# VGAX_board_rev_12_PAPER_VERSION_option_2.net
KiCad netlist of a schematic drawn in EAGLE
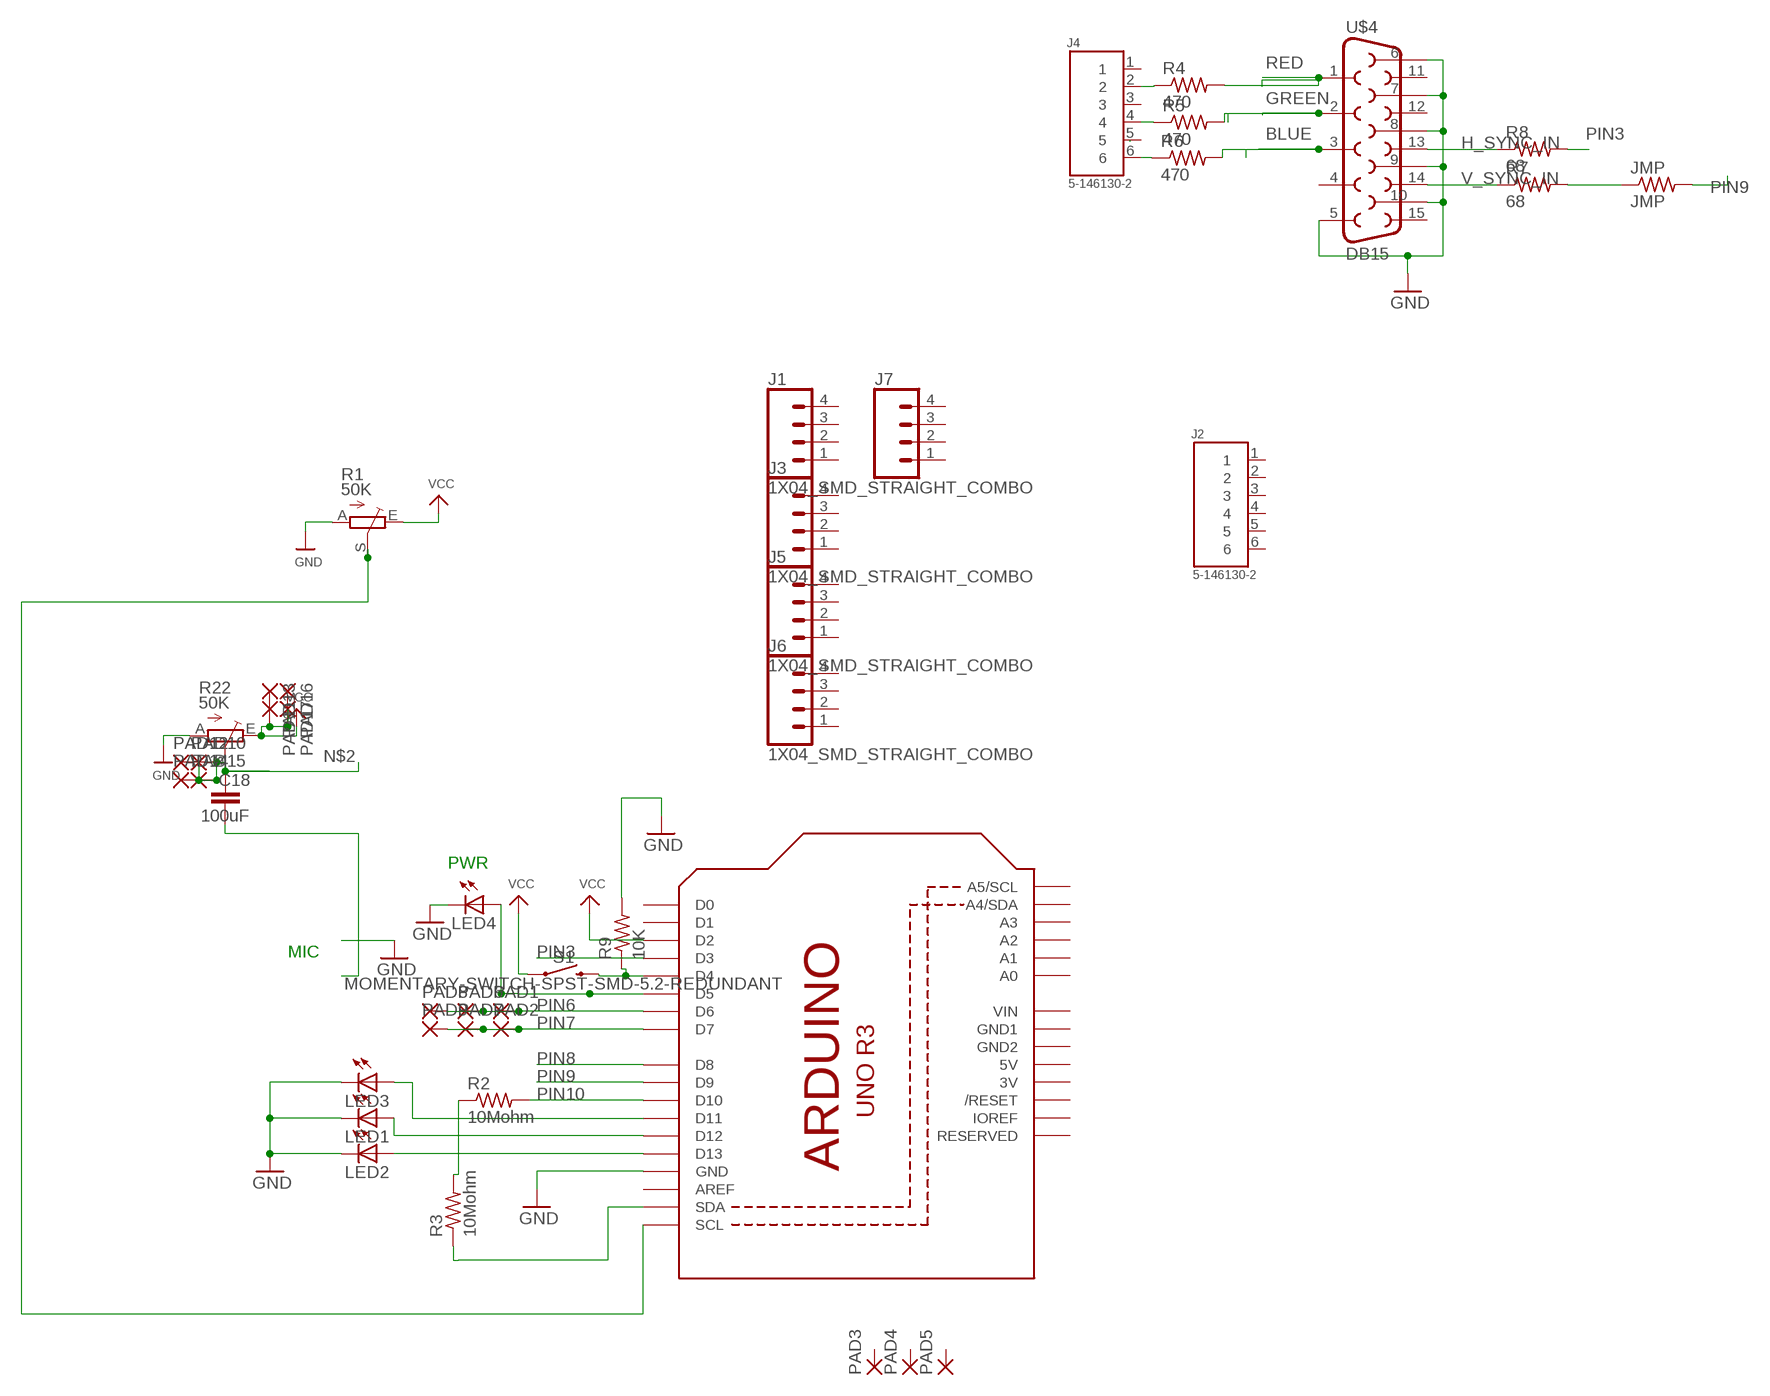
[diagram p0: schematic, sheet 1]

(export (version "E")
  (design (tool "Eeschema 10.0.6"))
  (components
    (comp (ref "C18")
      (value "100uF")
      (footprint "eagle-import:1206")
      (libsource (lib "eagle-import") (part "1.0UF-1206-50V-10%"))
    )
    (comp (ref "J1")
      (value "1X04_SMD_STRAIGHT_COMBO")
      (footprint "eagle-import:1X04_SMD_VERTICAL_COMBO")
      (libsource (lib "eagle-import") (part "CONN_04SMD_STRAIGHT_COMBO"))
    )
    (comp (ref "J2")
      (value "5-146130-2")
      (footprint "eagle-import:5-146130-2")
      (fields
        (field (name "DIGIKEY_PART_NUMBER") "5-146130-2-ND")
        (field (name "MANUFACTURER") "TE Connectivity AMP Connectors")
        (field (name "CREATED_BY") "PCBLayout.com")
      )
      (libsource (lib "eagle-import") (part "5-146130-2"))
    )
    (comp (ref "J3")
      (value "1X04_SMD_STRAIGHT_COMBO")
      (footprint "eagle-import:1X04_SMD_VERTICAL_COMBO")
      (libsource (lib "eagle-import") (part "CONN_04SMD_STRAIGHT_COMBO"))
    )
    (comp (ref "J4")
      (value "5-146130-2")
      (footprint "eagle-import:5-146130-2")
      (fields
        (field (name "DIGIKEY_PART_NUMBER") "5-146130-2-ND")
        (field (name "MANUFACTURER") "TE Connectivity AMP Connectors")
        (field (name "CREATED_BY") "PCBLayout.com")
      )
      (libsource (lib "eagle-import") (part "5-146130-2"))
    )
    (comp (ref "J5")
      (value "1X04_SMD_STRAIGHT_COMBO")
      (footprint "eagle-import:1X04_SMD_VERTICAL_COMBO")
      (libsource (lib "eagle-import") (part "CONN_04SMD_STRAIGHT_COMBO"))
    )
    (comp (ref "J6")
      (value "1X04_SMD_STRAIGHT_COMBO")
      (footprint "eagle-import:1X04_SMD_VERTICAL_COMBO")
      (libsource (lib "eagle-import") (part "CONN_04SMD_STRAIGHT_COMBO"))
    )
    (comp (ref "J7")
      (value "1X04_SMD_STRAIGHT_COMBO")
      (footprint "eagle-import:1X04_SMD_VERTICAL_COMBO")
      (libsource (lib "eagle-import") (part "CONN_04SMD_STRAIGHT_COMBO"))
    )
    (comp (ref "JMP")
      (value "JMP")
      (footprint "eagle-import:M1206")
      (libsource (lib "eagle-import") (part "R-US_M1206"))
    )
    (comp (ref "LED1")
      (value "LEDCHIPLED_1206")
      (footprint "eagle-import:CHIPLED_1206")
      (libsource (lib "eagle-import") (part "LEDCHIPLED_1206"))
    )
    (comp (ref "LED2")
      (value "LEDCHIPLED_1206")
      (footprint "eagle-import:CHIPLED_1206")
      (libsource (lib "eagle-import") (part "LEDCHIPLED_1206"))
    )
    (comp (ref "LED3")
      (value "LEDCHIPLED_1206")
      (footprint "eagle-import:CHIPLED_1206")
      (libsource (lib "eagle-import") (part "LEDCHIPLED_1206"))
    )
    (comp (ref "LED4")
      (value "LEDCHIPLED_1206")
      (footprint "eagle-import:CHIPLED_1206")
      (libsource (lib "eagle-import") (part "LEDCHIPLED_1206"))
    )
    (comp (ref "PAD1")
      (value "SMD2")
      (footprint "eagle-import:SMD1,27-2,54")
      (libsource (lib "eagle-import") (part "SMD2"))
    )
    (comp (ref "PAD2")
      (value "SMD2")
      (footprint "eagle-import:SMD1,27-2,54")
      (libsource (lib "eagle-import") (part "SMD2"))
    )
    (comp (ref "PAD3")
      (value "SMD2")
      (footprint "eagle-import:SMD1,27-2,54")
      (libsource (lib "eagle-import") (part "SMD2"))
    )
    (comp (ref "PAD4")
      (value "SMD2")
      (footprint "eagle-import:SMD1,27-2,54")
      (libsource (lib "eagle-import") (part "SMD2"))
    )
    (comp (ref "PAD5")
      (value "SMD2")
      (footprint "eagle-import:SMD1,27-2,54")
      (libsource (lib "eagle-import") (part "SMD2"))
    )
    (comp (ref "PAD6")
      (value "SMD2")
      (footprint "eagle-import:SMD1,27-2,54")
      (libsource (lib "eagle-import") (part "SMD2"))
    )
    (comp (ref "PAD7")
      (value "SMD2")
      (footprint "eagle-import:SMD1,27-2,54")
      (libsource (lib "eagle-import") (part "SMD2"))
    )
    (comp (ref "PAD8")
      (value "SMD2")
      (footprint "eagle-import:SMD1,27-2,54")
      (libsource (lib "eagle-import") (part "SMD2"))
    )
    (comp (ref "PAD9")
      (value "SMD2")
      (footprint "eagle-import:SMD1,27-2,54")
      (libsource (lib "eagle-import") (part "SMD2"))
    )
    (comp (ref "PAD10")
      (value "SMD2")
      (footprint "eagle-import:SMD1,27-2,54")
      (libsource (lib "eagle-import") (part "SMD2"))
    )
    (comp (ref "PAD11")
      (value "SMD2")
      (footprint "eagle-import:SMD1,27-2,54")
      (libsource (lib "eagle-import") (part "SMD2"))
    )
    (comp (ref "PAD12")
      (value "SMD2")
      (footprint "eagle-import:SMD1,27-2,54")
      (libsource (lib "eagle-import") (part "SMD2"))
    )
    (comp (ref "PAD13")
      (value "SMD2")
      (footprint "eagle-import:SMD1,27-2,54")
      (libsource (lib "eagle-import") (part "SMD2"))
    )
    (comp (ref "PAD14")
      (value "SMD2")
      (footprint "eagle-import:SMD1,27-2,54")
      (libsource (lib "eagle-import") (part "SMD2"))
    )
    (comp (ref "PAD15")
      (value "SMD2")
      (footprint "eagle-import:SMD1,27-2,54")
      (libsource (lib "eagle-import") (part "SMD2"))
    )
    (comp (ref "PAD16")
      (value "SMD2")
      (footprint "eagle-import:SMD1,27-2,54")
      (libsource (lib "eagle-import") (part "SMD2"))
    )
    (comp (ref "PAD17")
      (value "SMD2")
      (footprint "eagle-import:SMD1,27-2,54")
      (libsource (lib "eagle-import") (part "SMD2"))
    )
    (comp (ref "R1")
      (value "50K")
      (footprint "eagle-import:CA9V")
      (libsource (lib "eagle-import") (part "TRIM_EU-CA9V"))
    )
    (comp (ref "R2")
      (value "10Mohm")
      (footprint "eagle-import:M1206")
      (libsource (lib "eagle-import") (part "R-US_M1206"))
    )
    (comp (ref "R3")
      (value "10Mohm")
      (footprint "eagle-import:M1206")
      (libsource (lib "eagle-import") (part "R-US_M1206"))
    )
    (comp (ref "R4")
      (value "470")
      (footprint "eagle-import:M1206")
      (libsource (lib "eagle-import") (part "R-US_M1206"))
    )
    (comp (ref "R5")
      (value "470")
      (footprint "eagle-import:M1206")
      (libsource (lib "eagle-import") (part "R-US_M1206"))
    )
    (comp (ref "R6")
      (value "470")
      (footprint "eagle-import:M1206")
      (libsource (lib "eagle-import") (part "R-US_M1206"))
    )
    (comp (ref "R7")
      (value "68")
      (footprint "eagle-import:M1206")
      (libsource (lib "eagle-import") (part "R-US_M1206"))
    )
    (comp (ref "R8")
      (value "68")
      (footprint "eagle-import:M1206")
      (libsource (lib "eagle-import") (part "R-US_M1206"))
    )
    (comp (ref "R9")
      (value "10K")
      (footprint "eagle-import:M1206")
      (libsource (lib "eagle-import") (part "R-US_M1206"))
    )
    (comp (ref "R22")
      (value "50K")
      (footprint "eagle-import:CA9V")
      (libsource (lib "eagle-import") (part "TRIM_EU-CA9V"))
    )
    (comp (ref "S1")
      (value "MOMENTARY-SWITCH-SPST-SMD-5.2-REDUNDANT")
      (footprint "eagle-import:TACTILE_SWITCH_SMD_5.2MM")
      (libsource (lib "eagle-import") (part "MOMENTARY-SWITCH-SPST-SMD-5.2-REDUNDANT"))
    )
    (comp (ref "U$4")
      (value "DB15")
      (footprint "eagle-import:DB15")
      (libsource (lib "eagle-import") (part "DB15"))
    )
    (comp (ref "U1")
      (value "ARDUINOR3-BPLACE")
      (footprint "eagle-import:ARDUINOR3-BPLACE")
      (libsource (lib "eagle-import") (part "ARDUINOR3-BPLACE"))
    )
  )
  (nets
    (net (code "1") (name "/3V") (class "Default")
      (node (ref "U1") (pin "3V") (pinfunction "3V_3V") (pintype "power_in"))
    )
    (net (code "2") (name "/5V") (class "Default")
      (node (ref "U1") (pin "5V") (pinfunction "5V_5V") (pintype "power_in"))
    )
    (net (code "3") (name "/BLUE") (class "Default")
      (node (ref "R6") (pin "2") (pinfunction "2_2") (pintype "passive"))
      (node (ref "U$4") (pin "3") (pinfunction "3_3") (pintype "passive"))
    )
    (net (code "4") (name "/GND1") (class "Default")
      (node (ref "U1") (pin "GND1") (pinfunction "GND1_GND1") (pintype "power_in"))
    )
    (net (code "5") (name "/GND2") (class "Default")
      (node (ref "U1") (pin "GND2") (pinfunction "GND2_GND2") (pintype "power_in"))
    )
    (net (code "6") (name "/GREEN") (class "Default")
      (node (ref "R5") (pin "2") (pinfunction "2_2") (pintype "passive"))
      (node (ref "U$4") (pin "2") (pinfunction "2_2") (pintype "passive"))
    )
    (net (code "7") (name "/H_SYNC_IN") (class "Default")
      (node (ref "R8") (pin "1") (pinfunction "1_1") (pintype "passive"))
      (node (ref "U$4") (pin "13") (pinfunction "13_13") (pintype "passive"))
    )
    (net (code "8") (name "/N$2") (class "Default")
      (node (ref "C18") (pin "1") (pinfunction "1_1") (pintype "passive"))
      (node (ref "PAD10") (pin "1") (pinfunction "P_1") (pintype "passive"))
      (node (ref "PAD12") (pin "1") (pinfunction "P_1") (pintype "passive"))
      (node (ref "PAD14") (pin "1") (pinfunction "P_1") (pintype "passive"))
      (node (ref "PAD15") (pin "1") (pinfunction "P_1") (pintype "passive"))
      (node (ref "R22") (pin "S") (pinfunction "S_S") (pintype "passive"))
    )
    (net (code "9") (name "/PIN3") (class "Default")
      (node (ref "R8") (pin "2") (pinfunction "2_2") (pintype "passive"))
      (node (ref "U1") (pin "D3") (pinfunction "D3_D3") (pintype "bidirectional"))
    )
    (net (code "10") (name "/PIN6") (class "Default")
      (node (ref "PAD1") (pin "1") (pinfunction "P_1") (pintype "passive"))
      (node (ref "PAD6") (pin "1") (pinfunction "P_1") (pintype "passive"))
      (node (ref "PAD8") (pin "1") (pinfunction "P_1") (pintype "passive"))
      (node (ref "U1") (pin "D6") (pinfunction "D6_D6") (pintype "bidirectional"))
    )
    (net (code "11") (name "/PIN7") (class "Default")
      (node (ref "PAD2") (pin "1") (pinfunction "P_1") (pintype "passive"))
      (node (ref "PAD7") (pin "1") (pinfunction "P_1") (pintype "passive"))
      (node (ref "PAD9") (pin "1") (pinfunction "P_1") (pintype "passive"))
      (node (ref "U1") (pin "D7") (pinfunction "D7_D7") (pintype "bidirectional"))
    )
    (net (code "12") (name "/PIN8") (class "Default")
      (node (ref "R3") (pin "1") (pinfunction "1_1") (pintype "passive"))
      (node (ref "U1") (pin "D8") (pinfunction "D8_D8") (pintype "bidirectional"))
      (node (ref "U1") (pin "SDA") (pinfunction "SDA_SDA") (pintype "bidirectional"))
    )
    (net (code "13") (name "/PIN9") (class "Default")
      (node (ref "JMP") (pin "2") (pinfunction "2_2") (pintype "passive"))
      (node (ref "U1") (pin "D9") (pinfunction "D9_D9") (pintype "bidirectional"))
    )
    (net (code "14") (name "/PIN10") (class "Default")
      (node (ref "R2") (pin "2") (pinfunction "2_2") (pintype "passive"))
      (node (ref "U1") (pin "D10") (pinfunction "D10_D10") (pintype "bidirectional"))
    )
    (net (code "15") (name "/RED") (class "Default")
      (node (ref "R4") (pin "2") (pinfunction "2_2") (pintype "passive"))
      (node (ref "U$4") (pin "1") (pinfunction "1_1") (pintype "passive"))
    )
    (net (code "16") (name "/VIN") (class "Default")
      (node (ref "U1") (pin "VIN") (pinfunction "VIN_VIN") (pintype "power_in"))
    )
    (net (code "17") (name "/V_SYNC_IN") (class "Default")
      (node (ref "R7") (pin "1") (pinfunction "1_1") (pintype "passive"))
      (node (ref "U$4") (pin "14") (pinfunction "14_14") (pintype "passive"))
    )
    (net (code "18") (name "GND") (class "Default")
      (node (ref "LED1") (pin "C") (pinfunction "C_C") (pintype "passive"))
      (node (ref "LED2") (pin "C") (pinfunction "C_C") (pintype "passive"))
      (node (ref "LED3") (pin "C") (pinfunction "C_C") (pintype "passive"))
      (node (ref "LED4") (pin "C") (pinfunction "C_C") (pintype "passive"))
      (node (ref "R1") (pin "A") (pinfunction "A_A") (pintype "passive"))
      (node (ref "R22") (pin "A") (pinfunction "A_A") (pintype "passive"))
      (node (ref "R9") (pin "2") (pinfunction "2_2") (pintype "passive"))
      (node (ref "U$4") (pin "10") (pinfunction "10_10") (pintype "passive"))
      (node (ref "U$4") (pin "5") (pinfunction "5_5") (pintype "passive"))
      (node (ref "U$4") (pin "6") (pinfunction "6_6") (pintype "passive"))
      (node (ref "U$4") (pin "7") (pinfunction "7_7") (pintype "passive"))
      (node (ref "U$4") (pin "8") (pinfunction "8_8") (pintype "passive"))
      (node (ref "U$4") (pin "9") (pinfunction "9_9") (pintype "passive"))
      (node (ref "U1") (pin "GND") (pinfunction "GND_GND") (pintype "power_in"))
    )
    (net (code "19") (name "Net-(J4-Pad2)") (class "Default")
      (node (ref "J4") (pin "2") (pinfunction "2_2") (pintype "passive"))
      (node (ref "R4") (pin "1") (pinfunction "1_1") (pintype "passive"))
    )
    (net (code "20") (name "Net-(J4-Pad4)") (class "Default")
      (node (ref "J4") (pin "4") (pinfunction "4_4") (pintype "passive"))
      (node (ref "R5") (pin "1") (pinfunction "1_1") (pintype "passive"))
    )
    (net (code "21") (name "Net-(J4-Pad6)") (class "Default")
      (node (ref "J4") (pin "6") (pinfunction "6_6") (pintype "passive"))
      (node (ref "R6") (pin "1") (pinfunction "1_1") (pintype "passive"))
    )
    (net (code "22") (name "Net-(JMP-Pad1)") (class "Default")
      (node (ref "JMP") (pin "1") (pinfunction "1_1") (pintype "passive"))
      (node (ref "R7") (pin "2") (pinfunction "2_2") (pintype "passive"))
    )
    (net (code "23") (name "Net-(LED1-PadA)") (class "Default")
      (node (ref "LED1") (pin "A") (pinfunction "A_A") (pintype "passive"))
      (node (ref "U1") (pin "D12") (pinfunction "D12_D12") (pintype "bidirectional"))
    )
    (net (code "24") (name "Net-(LED2-PadA)") (class "Default")
      (node (ref "LED2") (pin "A") (pinfunction "A_A") (pintype "passive"))
      (node (ref "U1") (pin "D13") (pinfunction "D13_D13") (pintype "bidirectional"))
    )
    (net (code "25") (name "Net-(LED3-PadA)") (class "Default")
      (node (ref "LED3") (pin "A") (pinfunction "A_A") (pintype "passive"))
      (node (ref "U1") (pin "D11") (pinfunction "D11_D11") (pintype "bidirectional"))
    )
    (net (code "26") (name "Net-(LED4-PadA)") (class "Default")
      (node (ref "LED4") (pin "A") (pinfunction "A_A") (pintype "passive"))
      (node (ref "U1") (pin "D5") (pinfunction "D5_D5") (pintype "bidirectional"))
    )
    (net (code "27") (name "Net-(R1-PadS)") (class "Default")
      (node (ref "R1") (pin "S") (pinfunction "S_S") (pintype "passive"))
      (node (ref "U1") (pin "SCL") (pinfunction "SCL_SCL") (pintype "bidirectional"))
    )
    (net (code "28") (name "Net-(R2-Pad1)") (class "Default")
      (node (ref "R2") (pin "1") (pinfunction "1_1") (pintype "passive"))
      (node (ref "R3") (pin "2") (pinfunction "2_2") (pintype "passive"))
    )
    (net (code "29") (name "Net-(R9-Pad1)") (class "Default")
      (node (ref "R9") (pin "1") (pinfunction "1_1") (pintype "passive"))
      (node (ref "S1") (pin "3") (pinfunction "2_3") (pintype "passive"))
      (node (ref "S1") (pin "4") (pinfunction "2_4") (pintype "passive"))
      (node (ref "U1") (pin "D4") (pinfunction "D4_D4") (pintype "bidirectional"))
    )
    (net (code "30") (name "VCC") (class "Default")
      (node (ref "PAD11") (pin "1") (pinfunction "P_1") (pintype "passive"))
      (node (ref "PAD16") (pin "1") (pinfunction "P_1") (pintype "passive"))
      (node (ref "PAD17") (pin "1") (pinfunction "P_1") (pintype "passive"))
      (node (ref "R1") (pin "E") (pinfunction "E_E") (pintype "passive"))
      (node (ref "R22") (pin "E") (pinfunction "E_E") (pintype "passive"))
      (node (ref "S1") (pin "1") (pinfunction "1_1") (pintype "passive"))
      (node (ref "S1") (pin "2") (pinfunction "1_2") (pintype "passive"))
      (node (ref "U1") (pin "D2") (pinfunction "D2_D2") (pintype "bidirectional"))
    )
    (net (code "31") (name "unconnected-(C18-Pad2)") (class "Default")
      (node (ref "C18") (pin "2") (pinfunction "2_2") (pintype "passive"))
    )
    (net (code "32") (name "unconnected-(J1-Pad1)") (class "Default")
      (node (ref "J1") (pin "1") (pinfunction "1_1") (pintype "passive"))
    )
    (net (code "33") (name "unconnected-(J1-Pad2)") (class "Default")
      (node (ref "J1") (pin "2") (pinfunction "2_2") (pintype "passive"))
    )
    (net (code "34") (name "unconnected-(J1-Pad3)") (class "Default")
      (node (ref "J1") (pin "3") (pinfunction "3_3") (pintype "passive"))
    )
    (net (code "35") (name "unconnected-(J1-Pad4)") (class "Default")
      (node (ref "J1") (pin "4") (pinfunction "4_4") (pintype "passive"))
    )
    (net (code "36") (name "unconnected-(J2-Pad1)") (class "Default")
      (node (ref "J2") (pin "1") (pinfunction "1_1") (pintype "passive"))
    )
    (net (code "37") (name "unconnected-(J2-Pad2)") (class "Default")
      (node (ref "J2") (pin "2") (pinfunction "2_2") (pintype "passive"))
    )
    (net (code "38") (name "unconnected-(J2-Pad3)") (class "Default")
      (node (ref "J2") (pin "3") (pinfunction "3_3") (pintype "passive"))
    )
    (net (code "39") (name "unconnected-(J2-Pad4)") (class "Default")
      (node (ref "J2") (pin "4") (pinfunction "4_4") (pintype "passive"))
    )
    (net (code "40") (name "unconnected-(J2-Pad5)") (class "Default")
      (node (ref "J2") (pin "5") (pinfunction "5_5") (pintype "passive"))
    )
    (net (code "41") (name "unconnected-(J2-Pad6)") (class "Default")
      (node (ref "J2") (pin "6") (pinfunction "6_6") (pintype "passive"))
    )
    (net (code "42") (name "unconnected-(J3-Pad1)") (class "Default")
      (node (ref "J3") (pin "1") (pinfunction "1_1") (pintype "passive"))
    )
    (net (code "43") (name "unconnected-(J3-Pad2)") (class "Default")
      (node (ref "J3") (pin "2") (pinfunction "2_2") (pintype "passive"))
    )
    (net (code "44") (name "unconnected-(J3-Pad3)") (class "Default")
      (node (ref "J3") (pin "3") (pinfunction "3_3") (pintype "passive"))
    )
    (net (code "45") (name "unconnected-(J3-Pad4)") (class "Default")
      (node (ref "J3") (pin "4") (pinfunction "4_4") (pintype "passive"))
    )
    (net (code "46") (name "unconnected-(J4-Pad1)") (class "Default")
      (node (ref "J4") (pin "1") (pinfunction "1_1") (pintype "passive"))
    )
    (net (code "47") (name "unconnected-(J4-Pad3)") (class "Default")
      (node (ref "J4") (pin "3") (pinfunction "3_3") (pintype "passive"))
    )
    (net (code "48") (name "unconnected-(J4-Pad5)") (class "Default")
      (node (ref "J4") (pin "5") (pinfunction "5_5") (pintype "passive"))
    )
    (net (code "49") (name "unconnected-(J5-Pad1)") (class "Default")
      (node (ref "J5") (pin "1") (pinfunction "1_1") (pintype "passive"))
    )
    (net (code "50") (name "unconnected-(J5-Pad2)") (class "Default")
      (node (ref "J5") (pin "2") (pinfunction "2_2") (pintype "passive"))
    )
    (net (code "51") (name "unconnected-(J5-Pad3)") (class "Default")
      (node (ref "J5") (pin "3") (pinfunction "3_3") (pintype "passive"))
    )
    (net (code "52") (name "unconnected-(J5-Pad4)") (class "Default")
      (node (ref "J5") (pin "4") (pinfunction "4_4") (pintype "passive"))
    )
    (net (code "53") (name "unconnected-(J6-Pad1)") (class "Default")
      (node (ref "J6") (pin "1") (pinfunction "1_1") (pintype "passive"))
    )
    (net (code "54") (name "unconnected-(J6-Pad2)") (class "Default")
      (node (ref "J6") (pin "2") (pinfunction "2_2") (pintype "passive"))
    )
    (net (code "55") (name "unconnected-(J6-Pad3)") (class "Default")
      (node (ref "J6") (pin "3") (pinfunction "3_3") (pintype "passive"))
    )
    (net (code "56") (name "unconnected-(J6-Pad4)") (class "Default")
      (node (ref "J6") (pin "4") (pinfunction "4_4") (pintype "passive"))
    )
    (net (code "57") (name "unconnected-(J7-Pad1)") (class "Default")
      (node (ref "J7") (pin "1") (pinfunction "1_1") (pintype "passive"))
    )
    (net (code "58") (name "unconnected-(J7-Pad2)") (class "Default")
      (node (ref "J7") (pin "2") (pinfunction "2_2") (pintype "passive"))
    )
    (net (code "59") (name "unconnected-(J7-Pad3)") (class "Default")
      (node (ref "J7") (pin "3") (pinfunction "3_3") (pintype "passive"))
    )
    (net (code "60") (name "unconnected-(J7-Pad4)") (class "Default")
      (node (ref "J7") (pin "4") (pinfunction "4_4") (pintype "passive"))
    )
    (net (code "61") (name "unconnected-(PAD3-P-Pad1)") (class "Default")
      (node (ref "PAD3") (pin "1") (pinfunction "P_1") (pintype "passive"))
    )
    (net (code "62") (name "unconnected-(PAD4-P-Pad1)") (class "Default")
      (node (ref "PAD4") (pin "1") (pinfunction "P_1") (pintype "passive"))
    )
    (net (code "63") (name "unconnected-(PAD5-P-Pad1)") (class "Default")
      (node (ref "PAD5") (pin "1") (pinfunction "P_1") (pintype "passive"))
    )
    (net (code "64") (name "unconnected-(PAD13-P-Pad1)") (class "Default")
      (node (ref "PAD13") (pin "1") (pinfunction "P_1") (pintype "passive"))
    )
    (net (code "65") (name "unconnected-(U$4-Pad4)") (class "Default")
      (node (ref "U$4") (pin "4") (pinfunction "4_4") (pintype "passive"))
    )
    (net (code "66") (name "unconnected-(U$4-Pad11)") (class "Default")
      (node (ref "U$4") (pin "11") (pinfunction "11_11") (pintype "passive"))
    )
    (net (code "67") (name "unconnected-(U$4-Pad12)") (class "Default")
      (node (ref "U$4") (pin "12") (pinfunction "12_12") (pintype "passive"))
    )
    (net (code "68") (name "unconnected-(U$4-Pad15)") (class "Default")
      (node (ref "U$4") (pin "15") (pinfunction "15_15") (pintype "passive"))
    )
    (net (code "69") (name "unconnected-(U1-A4{slash}SDA-PadA4)") (class "Default")
      (node (ref "U1") (pin "A4") (pinfunction "A4/SDA_A4") (pintype "bidirectional"))
    )
    (net (code "70") (name "unconnected-(U1-A5{slash}SCL-PadA5)") (class "Default")
      (node (ref "U1") (pin "A5") (pinfunction "A5/SCL_A5") (pintype "bidirectional"))
    )
    (net (code "71") (name "unconnected-(U1-PadA0)") (class "Default")
      (node (ref "U1") (pin "A0") (pinfunction "A0_A0") (pintype "bidirectional"))
    )
    (net (code "72") (name "unconnected-(U1-PadA1)") (class "Default")
      (node (ref "U1") (pin "A1") (pinfunction "A1_A1") (pintype "bidirectional"))
    )
    (net (code "73") (name "unconnected-(U1-PadA2)") (class "Default")
      (node (ref "U1") (pin "A2") (pinfunction "A2_A2") (pintype "bidirectional"))
    )
    (net (code "74") (name "unconnected-(U1-PadA3)") (class "Default")
      (node (ref "U1") (pin "A3") (pinfunction "A3_A3") (pintype "bidirectional"))
    )
    (net (code "75") (name "unconnected-(U1-PadAREF)") (class "Default")
      (node (ref "U1") (pin "AREF") (pinfunction "AREF_AREF") (pintype "bidirectional"))
    )
    (net (code "76") (name "unconnected-(U1-PadD0)") (class "Default")
      (node (ref "U1") (pin "D0") (pinfunction "D0_D0") (pintype "bidirectional"))
    )
    (net (code "77") (name "unconnected-(U1-PadD1)") (class "Default")
      (node (ref "U1") (pin "D1") (pinfunction "D1_D1") (pintype "bidirectional"))
    )
    (net (code "78") (name "unconnected-(U1-PadIOREF)") (class "Default")
      (node (ref "U1") (pin "IOREF") (pinfunction "IOREF_IOREF") (pintype "output"))
    )
    (net (code "79") (name "unconnected-(U1-PadRESERVED)") (class "Default")
      (node (ref "U1") (pin "RESERVED") (pinfunction "RESERVED_RESERVED") (pintype "no_connect"))
    )
    (net (code "80") (name "unconnected-(U1-{slash}RESET-PadRESET)") (class "Default")
      (node (ref "U1") (pin "RESET") (pinfunction "/RESET_RESET") (pintype "bidirectional"))
    )
  )
)
